# shinobi_3V3_5v.net
KiCad netlist of a schematic drawn in EAGLE
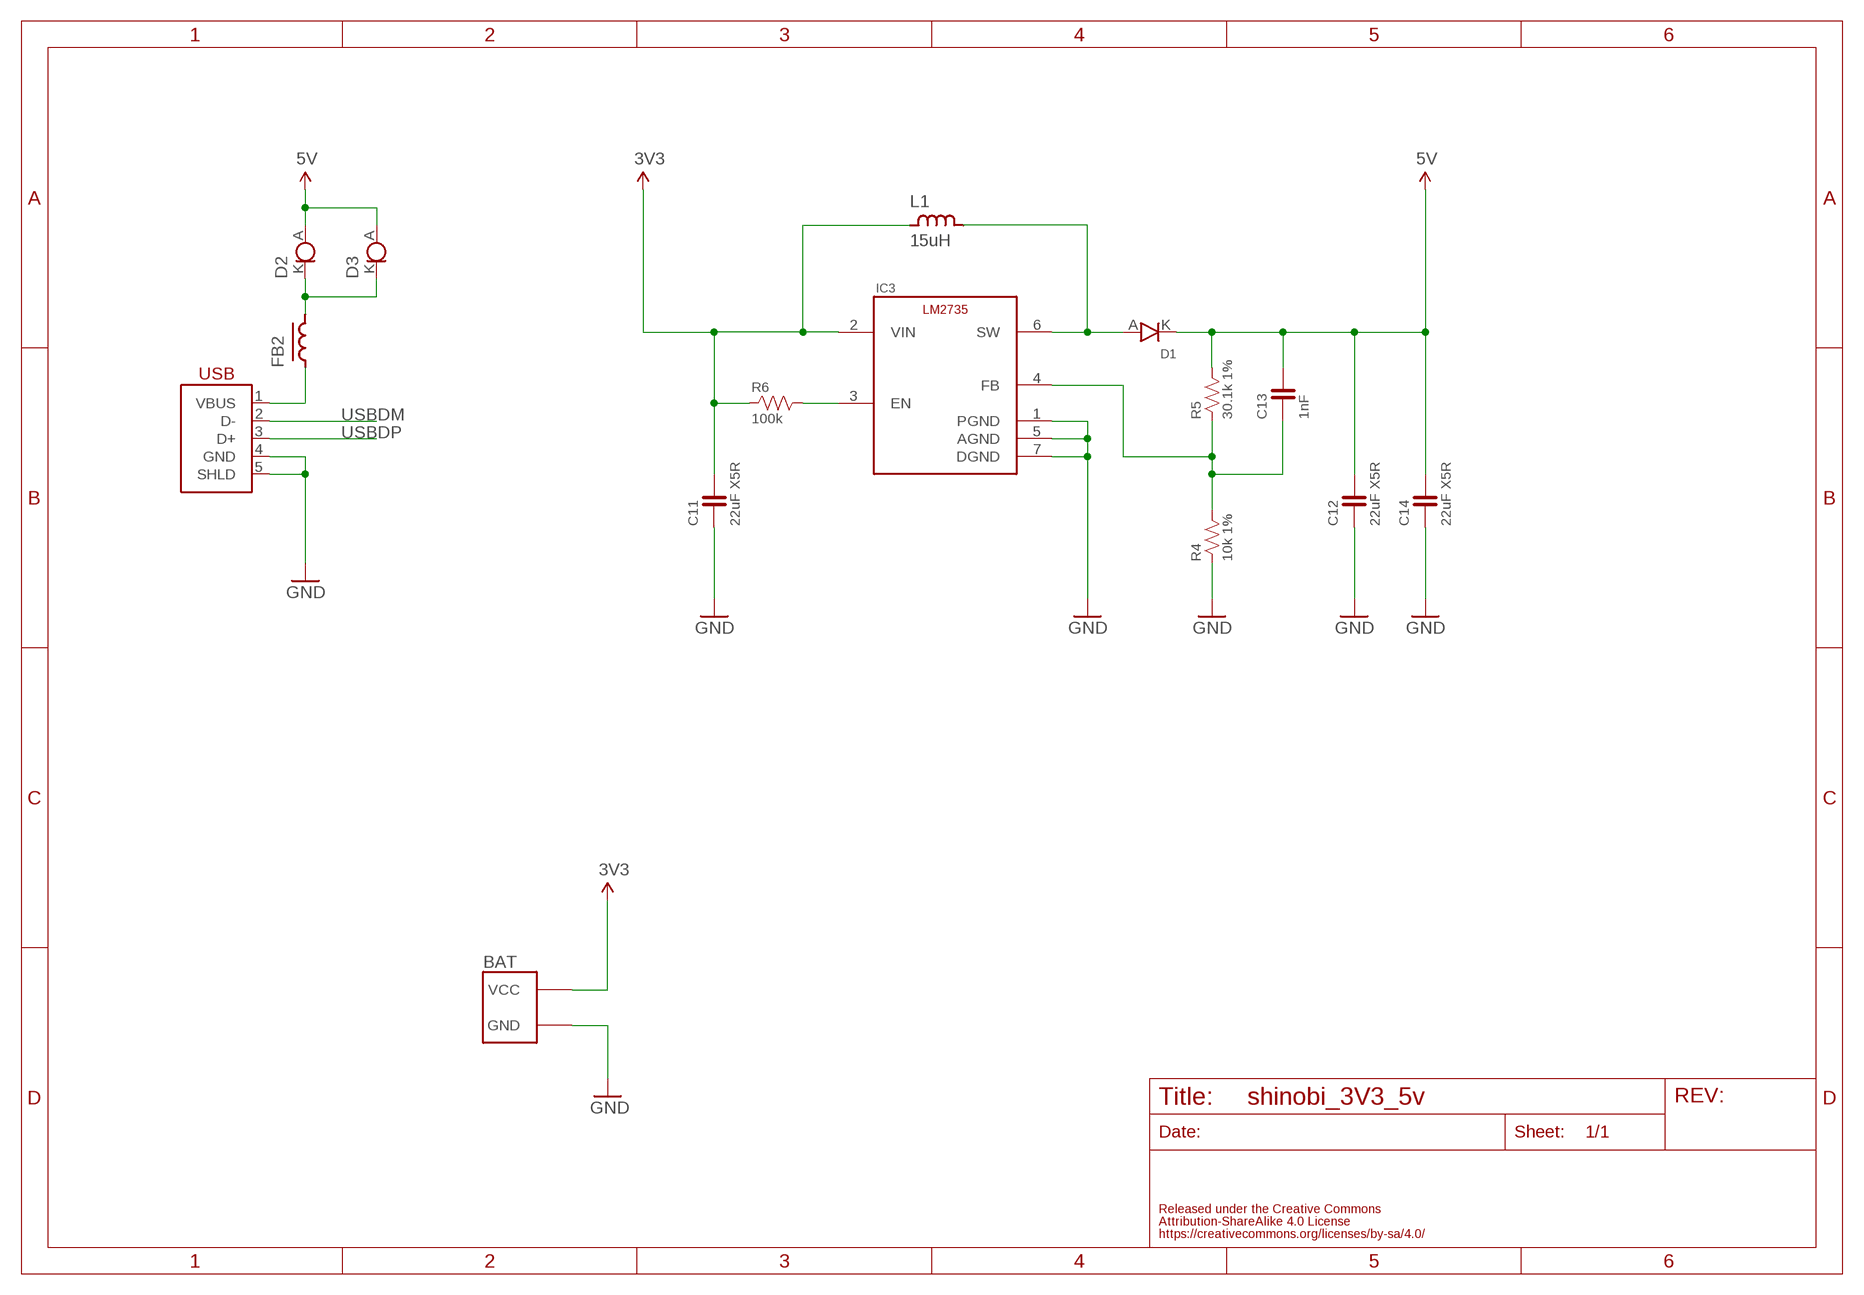
[diagram p0: schematic, sheet 1]

(export (version "E")
  (design (tool "Eeschema 10.0.6"))
  (components
    (comp (ref "BAT")
      (value "FABO_BRICK_2PIN_SIDE")
      (footprint "eagle-import:FABO_BRICK_2PIN_S02B−PASK-2_SILK")
      (libsource (lib "eagle-import") (part "FABO_BRICK_2PIN_SIDE"))
    )
    (comp (ref "C11")
      (value "22uF X5R")
      (footprint "eagle-import:0603-NARROW")
      (libsource (lib "eagle-import") (part "CAPACITOR-0603_NARROW"))
    )
    (comp (ref "C12")
      (value "22uF X5R")
      (footprint "eagle-import:0603-NARROW")
      (libsource (lib "eagle-import") (part "CAPACITOR-0603_NARROW"))
    )
    (comp (ref "C13")
      (value "1nF")
      (footprint "eagle-import:0603-NARROW")
      (libsource (lib "eagle-import") (part "CAPACITOR-0603_NARROW"))
    )
    (comp (ref "C14")
      (value "22uF X5R")
      (footprint "eagle-import:0603-NARROW")
      (libsource (lib "eagle-import") (part "CAPACITOR-0603_NARROW"))
    )
    (comp (ref "D1")
      (value "20V1A")
      (footprint "eagle-import:ST-MITE-FLAT")
      (libsource (lib "eagle-import") (part "DIODE-STPS120MF"))
    )
    (comp (ref "D2")
      (value "CRD_S-153T")
      (footprint "eagle-import:CRD-S-153T")
      (libsource (lib "eagle-import") (part "CRD_S-153T"))
    )
    (comp (ref "D3")
      (value "CRD_S-153T")
      (footprint "eagle-import:CRD-S-153T")
      (libsource (lib "eagle-import") (part "CRD_S-153T"))
    )
    (comp (ref "FB2")
      (value "FERRITEBEADS")
      (footprint "eagle-import:EIA0603")
      (libsource (lib "eagle-import") (part "FERRITEBEADS"))
    )
    (comp (ref "IC3")
      (value "LM2735YQSDX")
      (footprint "eagle-import:WSON-6")
      (libsource (lib "eagle-import") (part "LM2735YQSDX"))
    )
    (comp (ref "L1")
      (value "15uH")
      (footprint "eagle-import:NR6028")
      (libsource (lib "eagle-import") (part "INDUCTOR-NR6028"))
    )
    (comp (ref "R4")
      (value "10k 1%")
      (footprint "eagle-import:0603-NARROW")
      (libsource (lib "eagle-import") (part "RESISTOR-0603-NARROW"))
    )
    (comp (ref "R5")
      (value "30.1k 1%")
      (footprint "eagle-import:0603-NARROW")
      (libsource (lib "eagle-import") (part "RESISTOR-0603-NARROW"))
    )
    (comp (ref "R6")
      (value "100k")
      (footprint "eagle-import:0603-NARROW")
      (libsource (lib "eagle-import") (part "RESISTOR-0603-NARROW"))
    )
    (comp (ref "USB1")
      (value "USB-CONN_SMT")
      (footprint "eagle-import:SM05B-PASS")
      (libsource (lib "eagle-import") (part "USB-CONN_SMT"))
    )
  )
  (nets
    (net (code "1") (name "/USBDM") (class "Default")
      (node (ref "USB1") (pin "2") (pinfunction "D-_2") (pintype "bidirectional"))
    )
    (net (code "2") (name "/USBDP") (class "Default")
      (node (ref "USB1") (pin "3") (pinfunction "D+_3") (pintype "bidirectional"))
    )
    (net (code "3") (name "3V3") (class "Default")
      (node (ref "BAT") (pin "VCC") (pinfunction "VCC_VCC") (pintype "bidirectional"))
      (node (ref "C11") (pin "2") (pinfunction "2_2") (pintype "passive"))
      (node (ref "IC3") (pin "2") (pinfunction "VIN_2") (pintype "bidirectional"))
      (node (ref "L1") (pin "1") (pinfunction "1_1") (pintype "bidirectional"))
      (node (ref "R6") (pin "1") (pinfunction "1_1") (pintype "bidirectional"))
    )
    (net (code "4") (name "5V") (class "Default")
      (node (ref "C12") (pin "2") (pinfunction "2_2") (pintype "passive"))
      (node (ref "C13") (pin "2") (pinfunction "2_2") (pintype "passive"))
      (node (ref "C14") (pin "2") (pinfunction "2_2") (pintype "passive"))
      (node (ref "D1") (pin "K") (pinfunction "K_K") (pintype "bidirectional"))
      (node (ref "D2") (pin "A") (pinfunction "A_A") (pintype "bidirectional"))
      (node (ref "D3") (pin "A") (pinfunction "A_A") (pintype "bidirectional"))
      (node (ref "R5") (pin "2") (pinfunction "2_2") (pintype "bidirectional"))
    )
    (net (code "5") (name "GND") (class "Default")
      (node (ref "BAT") (pin "GND") (pinfunction "GND_GND") (pintype "bidirectional"))
      (node (ref "C11") (pin "1") (pinfunction "1_1") (pintype "passive"))
      (node (ref "C12") (pin "1") (pinfunction "1_1") (pintype "passive"))
      (node (ref "C14") (pin "1") (pinfunction "1_1") (pintype "passive"))
      (node (ref "IC3") (pin "1") (pinfunction "PGND_1") (pintype "bidirectional"))
      (node (ref "IC3") (pin "5") (pinfunction "AGND_5") (pintype "bidirectional"))
      (node (ref "IC3") (pin "7") (pinfunction "DGND_7") (pintype "bidirectional"))
      (node (ref "R4") (pin "1") (pinfunction "1_1") (pintype "bidirectional"))
      (node (ref "USB1") (pin "4") (pinfunction "GND_4") (pintype "bidirectional"))
      (node (ref "USB1") (pin "5") (pinfunction "SHLD_5") (pintype "bidirectional"))
    )
    (net (code "6") (name "Net-(D2-PadK)") (class "Default")
      (node (ref "D2") (pin "K") (pinfunction "K_K") (pintype "bidirectional"))
      (node (ref "D3") (pin "K") (pinfunction "K_K") (pintype "bidirectional"))
      (node (ref "FB2") (pin "2") (pinfunction "2_2") (pintype "bidirectional"))
    )
    (net (code "7") (name "Net-(IC3-EN)") (class "Default")
      (node (ref "IC3") (pin "3") (pinfunction "EN_3") (pintype "bidirectional"))
      (node (ref "R6") (pin "2") (pinfunction "2_2") (pintype "bidirectional"))
    )
    (net (code "8") (name "Net-(IC3-FB)") (class "Default")
      (node (ref "C13") (pin "1") (pinfunction "1_1") (pintype "passive"))
      (node (ref "IC3") (pin "4") (pinfunction "FB_4") (pintype "bidirectional"))
      (node (ref "R4") (pin "2") (pinfunction "2_2") (pintype "bidirectional"))
      (node (ref "R5") (pin "1") (pinfunction "1_1") (pintype "bidirectional"))
    )
    (net (code "9") (name "Net-(IC3-SW)") (class "Default")
      (node (ref "D1") (pin "A") (pinfunction "A_A") (pintype "bidirectional"))
      (node (ref "IC3") (pin "6") (pinfunction "SW_6") (pintype "bidirectional"))
      (node (ref "L1") (pin "2") (pinfunction "2_2") (pintype "bidirectional"))
    )
    (net (code "10") (name "Net-(USB1-VBUS)") (class "Default")
      (node (ref "FB2") (pin "1") (pinfunction "1_1") (pintype "bidirectional"))
      (node (ref "USB1") (pin "1") (pinfunction "VBUS_1") (pintype "bidirectional"))
    )
  )
)
